# Sensor_Glove_Power-X01.net
KiCad netlist of a schematic drawn in Altium Designer
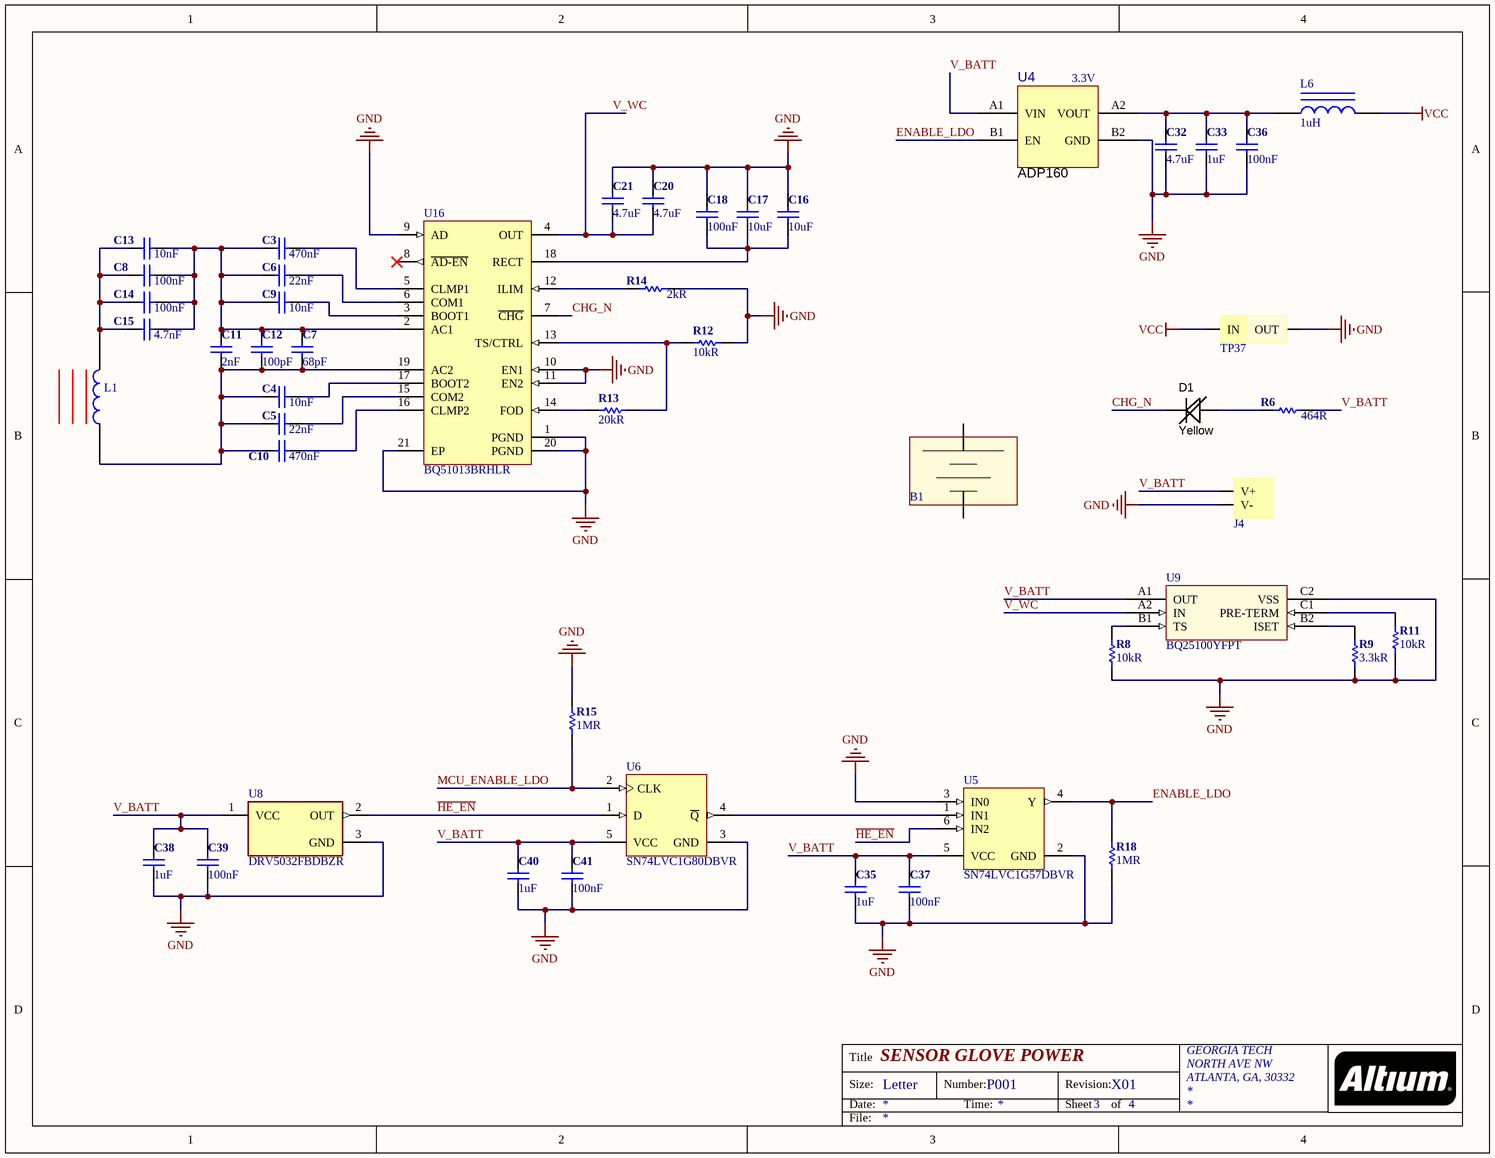
[diagram p0: Sensor_Glove_Power-X01.SchDoc]

(export (version "E")
  (design (tool "Eeschema 10.0.6"))
  (components
    (comp (ref "B1")
      (value "40 mAh BATTERY")
      (footprint "BATTERY")
      (description "Lithium Battery 3.7V 40mAh Rechargeable")
      (fields (field (name "MANUFACTURER") "SparkFun") (field (name "MANUFACTURER PART NUMBER") "PRT-13852"))
      (libsource (lib "Sensor_Glove-X01") (part "BATTERY"))
    )
    (comp (ref "C3")
      (value "470nF")
      (footprint "C0402")
      (fields
        (field (name "MANUFACTURER") "Murata")
        (field (name "MANUFACTURER PART NUMBER") "GRT155R61E474ME01D")
        (field (name "TOLERANCE") "20%")
      )
      (libsource (lib "DB-X01") (part "C-0402(1005)"))
    )
    (comp (ref "C4")
      (value "10nF")
      (footprint "C0402")
      (fields
        (field (name "MANUFACTURER") "KEMET")
        (field (name "MANUFACTURER PART NUMBER") "C0402C103J3RACTU")
        (field (name "TOLERANCE") "5%")
      )
      (libsource (lib "DB-X01") (part "C-0402(1005)"))
    )
    (comp (ref "C5")
      (value "22nF")
      (footprint "C0402")
      (fields
        (field (name "MANUFACTURER") "Murata")
        (field (name "MANUFACTURER PART NUMBER") "GRM155R71E223KA61D")
        (field (name "TOLERANCE") "10%")
      )
      (libsource (lib "DB-X01") (part "C-0402(1005)"))
    )
    (comp (ref "C6")
      (value "22nF")
      (footprint "C0402")
      (fields
        (field (name "MANUFACTURER") "Murata")
        (field (name "MANUFACTURER PART NUMBER") "GRM155R71E223KA61D")
        (field (name "TOLERANCE") "10%")
      )
      (libsource (lib "DB-X01") (part "C-0402(1005)"))
    )
    (comp (ref "C7")
      (value "68pF")
      (footprint "C0402")
      (fields
        (field (name "MANUFACTURER") "KEMET")
        (field (name "MANUFACTURER PART NUMBER") "CBR04C680F3GAC")
        (field (name "TOLERANCE") "1%")
      )
      (libsource (lib "DB-X01") (part "C-0402(1005)"))
    )
    (comp (ref "C8")
      (value "100nF")
      (footprint "C0402")
      (fields
        (field (name "MANUFACTURER") "Taiyo Yuden")
        (field (name "MANUFACTURER PART NUMBER") "TMK105BJ104KV-F")
        (field (name "TOLERANCE") "10%")
      )
      (libsource (lib "DB-X01") (part "C-0402(1005)"))
    )
    (comp (ref "C9")
      (value "10nF")
      (footprint "C0402")
      (fields
        (field (name "MANUFACTURER") "KEMET")
        (field (name "MANUFACTURER PART NUMBER") "C0402C103J3RACTU")
        (field (name "TOLERANCE") "5%")
      )
      (libsource (lib "DB-X01") (part "C-0402(1005)"))
    )
    (comp (ref "C10")
      (value "470nF")
      (footprint "C0402")
      (fields
        (field (name "MANUFACTURER") "Murata")
        (field (name "MANUFACTURER PART NUMBER") "GRT155R61E474ME01D")
        (field (name "TOLERANCE") "20%")
      )
      (libsource (lib "DB-X01") (part "C-0402(1005)"))
    )
    (comp (ref "C11")
      (value "2nF")
      (footprint "C0402")
      (fields
        (field (name "MANUFACTURER") "KEMET")
        (field (name "MANUFACTURER PART NUMBER") "C0402C202J3GACTU")
        (field (name "TOLERANCE") "5%")
      )
      (libsource (lib "DB-X01") (part "C-0402(1005)"))
    )
    (comp (ref "C12")
      (value "100pF")
      (footprint "C0402")
      (fields
        (field (name "MANUFACTURER") "KEMET")
        (field (name "MANUFACTURER PART NUMBER") "CBR04C101F3GAC")
        (field (name "TOLERANCE") "1%")
      )
      (libsource (lib "DB-X01") (part "C-0402(1005)"))
    )
    (comp (ref "C13")
      (value "10nF")
      (footprint "C0402")
      (fields
        (field (name "MANUFACTURER") "Yageo")
        (field (name "MANUFACTURER PART NUMBER") "CC0402JRX7R8BB103")
        (field (name "TOLERANCE") "5%")
      )
      (libsource (lib "DB-X01") (part "C-0402(1005)"))
    )
    (comp (ref "C14")
      (value "100nF")
      (footprint "C0402")
      (fields
        (field (name "MANUFACTURER") "Taiyo Yuden")
        (field (name "MANUFACTURER PART NUMBER") "TMK105BJ104KV-F")
        (field (name "TOLERANCE") "10%")
      )
      (libsource (lib "DB-X01") (part "C-0402(1005)"))
    )
    (comp (ref "C15")
      (value "4.7nF")
      (footprint "C0402")
      (fields
        (field (name "MANUFACTURER") "Yageo")
        (field (name "MANUFACTURER PART NUMBER") "CC0402JRX7R8BB472")
        (field (name "TOLERANCE") "5%")
      )
      (libsource (lib "DB-X01") (part "C-0402(1005)"))
    )
    (comp (ref "C16")
      (value "10uF")
      (footprint "C0603")
      (fields
        (field (name "MANUFACTURER") "Murata")
        (field (name "MANUFACTURER PART NUMBER") "GRM188R61E106MA73J")
        (field (name "TOLERANCE") "20%")
      )
      (libsource (lib "DB-X01") (part "C-0603(1608)"))
    )
    (comp (ref "C17")
      (value "10uF")
      (footprint "C0603")
      (fields
        (field (name "MANUFACTURER") "Murata")
        (field (name "MANUFACTURER PART NUMBER") "GRM188R61E106MA73J")
        (field (name "TOLERANCE") "20%")
      )
      (libsource (lib "DB-X01") (part "C-0603(1608)"))
    )
    (comp (ref "C18")
      (value "100nF")
      (footprint "C0603")
      (fields
        (field (name "MANUFACTURER") "Yageo")
        (field (name "MANUFACTURER PART NUMBER") "CC0402ZRY5V8BB104")
        (field (name "TOLERANCE") "80%")
      )
      (libsource (lib "DB-X01") (part "C-0603(1608)"))
    )
    (comp (ref "C20")
      (value "4.7uF")
      (footprint "C0402")
      (description "0402 10 V 4.7 uF ±20% Tolerance X5R Multilayer Ceramic Chip Capacitor")
      (fields
        (field (name "MANUFACTURER") "Murata")
        (field (name "MANUFACTURER PART NUMBER") "GRM155R61A475MEAAD")
      )
      (libsource (lib "DB-X01") (part "C-0402(1005)"))
    )
    (comp (ref "C21")
      (value "4.7uF")
      (footprint "C0402")
      (description "0402 10 V 4.7 uF ±20% Tolerance X5R Multilayer Ceramic Chip Capacitor")
      (fields
        (field (name "MANUFACTURER") "Murata")
        (field (name "MANUFACTURER PART NUMBER") "GRM155R61A475MEAAD")
      )
      (libsource (lib "DB-X01") (part "C-0402(1005)"))
    )
    (comp (ref "C32")
      (value "4.7uF")
      (footprint "C0402")
      (description "0402 10 V 4.7 uF ±20% Tolerance X5R Multilayer Ceramic Chip Capacitor")
      (fields
        (field (name "MANUFACTURER") "Murata")
        (field (name "MANUFACTURER PART NUMBER") "GRM155R61A475MEAAD")
      )
      (libsource (lib "DB-X01") (part "C-0402(1005)"))
    )
    (comp (ref "C33")
      (value "1uF")
      (footprint "C0402")
      (fields
        (field (name "MANUFACTURER") "Yageo")
        (field (name "MANUFACTURER PART NUMBER") "CC0402MRX5R5BB105")
        (field (name "TOLERANCE") "20%")
      )
      (libsource (lib "DB-X01") (part "C-0402(1005)"))
    )
    (comp (ref "C35")
      (value "1uF")
      (footprint "C0402")
      (fields
        (field (name "MANUFACTURER") "Yageo")
        (field (name "MANUFACTURER PART NUMBER") "CC0402MRX5R5BB105")
        (field (name "TOLERANCE") "20%")
      )
      (libsource (lib "DB-X01") (part "C-0402(1005)"))
    )
    (comp (ref "C36")
      (value "100nF")
      (footprint "C0402")
      (fields
        (field (name "MANUFACTURER") "Taiyo Yuden")
        (field (name "MANUFACTURER PART NUMBER") "TMK105BJ104KV-F")
        (field (name "TOLERANCE") "10%")
      )
      (libsource (lib "DB-X01") (part "C-0402(1005)"))
    )
    (comp (ref "C37")
      (value "100nF")
      (footprint "C0402")
      (fields
        (field (name "MANUFACTURER") "Taiyo Yuden")
        (field (name "MANUFACTURER PART NUMBER") "TMK105BJ104KV-F")
        (field (name "TOLERANCE") "10%")
      )
      (libsource (lib "DB-X01") (part "C-0402(1005)"))
    )
    (comp (ref "C38")
      (value "1uF")
      (footprint "C0402")
      (fields
        (field (name "MANUFACTURER") "Yageo")
        (field (name "MANUFACTURER PART NUMBER") "CC0402MRX5R5BB105")
        (field (name "TOLERANCE") "20%")
      )
      (libsource (lib "DB-X01") (part "C-0402(1005)"))
    )
    (comp (ref "C39")
      (value "100nF")
      (footprint "C0402")
      (fields
        (field (name "MANUFACTURER") "Taiyo Yuden")
        (field (name "MANUFACTURER PART NUMBER") "TMK105BJ104KV-F")
        (field (name "TOLERANCE") "10%")
      )
      (libsource (lib "DB-X01") (part "C-0402(1005)"))
    )
    (comp (ref "C40")
      (value "1uF")
      (footprint "C0402")
      (fields
        (field (name "MANUFACTURER") "Yageo")
        (field (name "MANUFACTURER PART NUMBER") "CC0402MRX5R5BB105")
        (field (name "TOLERANCE") "20%")
      )
      (libsource (lib "DB-X01") (part "C-0402(1005)"))
    )
    (comp (ref "C41")
      (value "100nF")
      (footprint "C0402")
      (fields
        (field (name "MANUFACTURER") "Taiyo Yuden")
        (field (name "MANUFACTURER PART NUMBER") "TMK105BJ104KV-F")
        (field (name "TOLERANCE") "10%")
      )
      (libsource (lib "DB-X01") (part "C-0402(1005)"))
    )
    (comp (ref "D1")
      (value "Yellow")
      (footprint "LED_0402")
      (description "Single Color LED, Super Bright Yellow, Water Clear, 0.8mm")
      (fields
        (field (name "MANUFACTURER") "Kingbright")
        (field (name "MANUFACTURER PART NUMBER") "APHHS1005SYCK")
      )
      (libsource (lib "DB-X01") (part "LED_0402(1005)"))
    )
    (comp (ref "J4")
      (value "JUMPER WITH 40 mAh BATTERY")
      (footprint "JUMPER_BATTERY")
      (description "Lithium Battery 3.7V 40mAh Rechargeable")
      (fields (field (name "MANUFACTURER") "SparkFun") (field (name "MANUFACTURER PART NUMBER") "PRT-13852"))
      (libsource (lib "Sensor_Glove-X01") (part "JUMPER_BATTERY"))
    )
    (comp (ref "L1")
      (value "WIRELESS CHARGING COIL, RECEIVER")
      (footprint "760308101219")
      (description "General Purpose Inductor, 11.8uH, 10%, 1 Element")
      (fields
        (field (name "MANUFACTURER") "Wurth Electronics")
        (field (name "MANUFACTURER PART NUMBER") "760308101219")
      )
      (libsource (lib "DB-X01") (part "WIRELESS_CHARGING_COIL"))
    )
    (comp (ref "L6")
      (value "1uH")
      (footprint "L0402")
      (description "General Purpose Inductor, 1uH, 20%, 1 Element, Ferrite-Core, SMD, 0402")
      (fields
        (field (name "MANUFACTURER") "TDK")
        (field (name "MANUFACTURER PART NUMBER") "MLZ1005M1R0WT000")
      )
      (libsource (lib "DB-X01") (part "Inductor Iron"))
    )
    (comp (ref "R6")
      (value "464R")
      (footprint "R0402")
      (fields
        (field (name "MANUFACTURER") "Yageo")
        (field (name "MANUFACTURER PART NUMBER") "RC0402FR-07464RL")
        (field (name "TOLERANCE") "1%")
      )
      (libsource (lib "DB-X01") (part "R-0402(1005)"))
    )
    (comp (ref "R8")
      (value "10kR")
      (footprint "R0402")
      (fields
        (field (name "MANUFACTURER") "Yageo")
        (field (name "MANUFACTURER PART NUMBER") "AC0402FR-0710KL")
        (field (name "TOLERANCE") "1%")
      )
      (libsource (lib "DB-X01") (part "R-0402(1005)"))
    )
    (comp (ref "R9")
      (value "3.3kR")
      (footprint "R0402")
      (fields
        (field (name "MANUFACTURER") "Yageo")
        (field (name "MANUFACTURER PART NUMBER") "AC0402FR-073K3L")
        (field (name "TOLERANCE") "1%")
      )
      (libsource (lib "DB-X01") (part "R-0402(1005)"))
    )
    (comp (ref "R11")
      (value "10kR")
      (footprint "R0402")
      (fields
        (field (name "MANUFACTURER") "Yageo")
        (field (name "MANUFACTURER PART NUMBER") "AC0402FR-0710KL")
        (field (name "TOLERANCE") "1%")
      )
      (libsource (lib "DB-X01") (part "R-0402(1005)"))
    )
    (comp (ref "R12")
      (value "10kR")
      (footprint "R0402")
      (fields
        (field (name "MANUFACTURER") "Yageo")
        (field (name "MANUFACTURER PART NUMBER") "AC0402FR-0710KL")
        (field (name "TOLERANCE") "1%")
      )
      (libsource (lib "DB-X01") (part "R-0402(1005)"))
    )
    (comp (ref "R13")
      (value "20kR")
      (footprint "R0402")
      (fields
        (field (name "MANUFACTURER") "Yageo")
        (field (name "MANUFACTURER PART NUMBER") "AC0402FR-0720KL")
        (field (name "TOLERANCE") "1%")
      )
      (libsource (lib "DB-X01") (part "R-0402(1005)"))
    )
    (comp (ref "R14")
      (value "2kR")
      (footprint "R0402")
      (fields
        (field (name "MANUFACTURER") "Yageo")
        (field (name "MANUFACTURER PART NUMBER") "AC0402FR-072KL")
        (field (name "TOLERANCE") "1%")
      )
      (libsource (lib "DB-X01") (part "R-0402(1005)"))
    )
    (comp (ref "R15")
      (value "1MR")
      (footprint "R0402")
      (fields
        (field (name "MANUFACTURER") "Yageo")
        (field (name "MANUFACTURER PART NUMBER") "AC0402FR-071ML")
        (field (name "TOLERANCE") "1%")
      )
      (libsource (lib "Sensor_Glove-X01") (part "R-0402(1005)"))
    )
    (comp (ref "R18")
      (value "1MR")
      (footprint "R0402")
      (fields
        (field (name "MANUFACTURER") "Yageo")
        (field (name "MANUFACTURER PART NUMBER") "AC0402FR-071ML")
        (field (name "TOLERANCE") "1%")
      )
      (libsource (lib "Sensor_Glove-X01") (part "R-0402(1005)"))
    )
    (comp (ref "TP37")
      (value "JUMPER")
      (footprint "JUMPER")
      (description "SHUNT LP W/HANDLE 2 POS 30AU")
      (fields
        (field (name "MANUFACTURER") "TE Connectivity")
        (field (name "MANUFACTURER PART NUMBER") "8815452")
      )
      (libsource (lib "DB-X02") (part "JUMPER"))
    )
    (comp (ref "U4")
      (value "ADP160")
      (footprint "ADP160")
      (description "Fixed Positive LDO Regulator, 3.3V, 0.195V Dropout, CMOS, PBGA4")
      (fields
        (field (name "MANUFACTURER") "Analog Devices")
        (field (name "MANUFACTURER PART NUMBER") "ADP160ACBZ-3.3-R7")
        (field (name "OUTPUT VOLTAGE") "3.3V")
      )
      (libsource (lib "DB-X01") (part "ADP160-3_3V"))
    )
    (comp (ref "U5")
      (value "SN74LVC1G57DBVR")
      (footprint "DBV0006A_M")
      (description "CONFIGURABLE MULTIPLE-FUNCTION GATE, DBV0006A, LARGE T&R")
      (fields (field (name "MANUFACTURER") "Texas Instruments"))
      (libsource (lib "Altium Content Vault") (part "TI-SN74XXX1GXX-6"))
    )
    (comp (ref "U6")
      (value "SN74LVC1G80DBVR")
      (footprint "DBV0005A_N")
      (description "Single Positive-Edge-Triggered D-Type Flip-Flop, DBV0005A, LARGE T&R")
      (fields (field (name "MANUFACTURER") "Texas Instruments"))
      (libsource (lib "Altium Content Vault") (part "TI-SN74XXX1G80-5"))
    )
    (comp (ref "U8")
      (value "DRV5032FBDBZR")
      (footprint "FP-DBZ0003A-MFG")
      (description "LP HALL 32FBDBZR")
      (fields (field (name "MANUFACTURER") "Texas Instruments"))
      (libsource (lib "Altium Content Vault") (part "2ac151be60cf6bda0d169f73a696793"))
    )
    (comp (ref "U9")
      (value "BQ25100YFPT")
      (footprint "YZP0006")
      (description "Power Supply Support Circuit")
      (fields (field (name "MANUFACTURER") "Texas Instruments"))
      (libsource (lib "Sensor_Glove-X01") (part "BQ25100YFPT"))
    )
    (comp (ref "U16")
      (value "BQ51013BRHLR")
      (footprint "BQ51013BRHLR")
      (fields (field (name "MANUFACTURER") "Texas Instruments"))
      (libsource (lib "DB-X01") (part "TI-BQ51013B-RHL20"))
    )
  )
  (nets
    (net (code "1") (name "/CHG_N") (class "Default")
      (node (ref "D1") (pin "K") (pinfunction "K_K") (pintype "passive"))
      (node (ref "U16") (pin "7") (pinfunction "~{CHG}_7") (pintype "open_collector"))
    )
    (net (code "2") (name "/ENABLE_LDO") (class "Default")
      (node (ref "R18") (pin "1") (pinfunction "1_1") (pintype "passive"))
      (node (ref "U4") (pin "B1") (pinfunction "EN_B1") (pintype "passive"))
      (node (ref "U5") (pin "4") (pinfunction "Y_4") (pintype "output"))
    )
    (net (code "3") (name "/MCU_ENABLE_LDO") (class "Default")
      (node (ref "R15") (pin "2") (pinfunction "2_2") (pintype "passive"))
      (node (ref "U6") (pin "2") (pinfunction "CLK_2") (pintype "input"))
    )
    (net (code "4") (name "/V_BATT") (class "Default")
      (node (ref "C35") (pin "1") (pinfunction "1_1") (pintype "passive"))
      (node (ref "C37") (pin "2") (pinfunction "2_2") (pintype "passive"))
      (node (ref "C38") (pin "1") (pinfunction "1_1") (pintype "passive"))
      (node (ref "C39") (pin "2") (pinfunction "2_2") (pintype "passive"))
      (node (ref "C40") (pin "1") (pinfunction "1_1") (pintype "passive"))
      (node (ref "C41") (pin "2") (pinfunction "2_2") (pintype "passive"))
      (node (ref "J4") (pin "1") (pinfunction "V+_1") (pintype "passive"))
      (node (ref "R6") (pin "2") (pinfunction "2_2") (pintype "passive"))
      (node (ref "U4") (pin "A1") (pinfunction "VIN_A1") (pintype "passive"))
      (node (ref "U5") (pin "5") (pinfunction "VCC_5") (pintype "power_in"))
      (node (ref "U6") (pin "5") (pinfunction "VCC_5") (pintype "power_in"))
      (node (ref "U8") (pin "1") (pinfunction "VCC_1") (pintype "power_in"))
      (node (ref "U9") (pin "A1") (pinfunction "OUT_A1") (pintype "power_in"))
    )
    (net (code "5") (name "/V_WC") (class "Default")
      (node (ref "C20") (pin "2") (pinfunction "2_2") (pintype "passive"))
      (node (ref "C21") (pin "2") (pinfunction "2_2") (pintype "passive"))
      (node (ref "U16") (pin "4") (pinfunction "OUT_4") (pintype "power_in"))
      (node (ref "U9") (pin "A2") (pinfunction "IN_A2") (pintype "input"))
    )
    (net (code "6") (name "/~{HE_EN}") (class "Default")
      (node (ref "U5") (pin "6") (pinfunction "IN2_6") (pintype "input"))
      (node (ref "U6") (pin "1") (pinfunction "D_1") (pintype "input"))
      (node (ref "U8") (pin "2") (pinfunction "OUT_2") (pintype "output"))
    )
    (net (code "7") (name "GND") (class "Default")
      (node (ref "C16") (pin "2") (pinfunction "2_2") (pintype "passive"))
      (node (ref "C17") (pin "2") (pinfunction "2_2") (pintype "passive"))
      (node (ref "C18") (pin "2") (pinfunction "2_2") (pintype "passive"))
      (node (ref "C20") (pin "1") (pinfunction "1_1") (pintype "passive"))
      (node (ref "C21") (pin "1") (pinfunction "1_1") (pintype "passive"))
      (node (ref "C32") (pin "2") (pinfunction "2_2") (pintype "passive"))
      (node (ref "C33") (pin "2") (pinfunction "2_2") (pintype "passive"))
      (node (ref "C35") (pin "2") (pinfunction "2_2") (pintype "passive"))
      (node (ref "C36") (pin "1") (pinfunction "1_1") (pintype "passive"))
      (node (ref "C37") (pin "1") (pinfunction "1_1") (pintype "passive"))
      (node (ref "C38") (pin "2") (pinfunction "2_2") (pintype "passive"))
      (node (ref "C39") (pin "1") (pinfunction "1_1") (pintype "passive"))
      (node (ref "C40") (pin "2") (pinfunction "2_2") (pintype "passive"))
      (node (ref "C41") (pin "1") (pinfunction "1_1") (pintype "passive"))
      (node (ref "J4") (pin "2") (pinfunction "V-_2") (pintype "passive"))
      (node (ref "R11") (pin "1") (pinfunction "1_1") (pintype "passive"))
      (node (ref "R12") (pin "2") (pinfunction "2_2") (pintype "passive"))
      (node (ref "R14") (pin "2") (pinfunction "2_2") (pintype "passive"))
      (node (ref "R15") (pin "1") (pinfunction "1_1") (pintype "passive"))
      (node (ref "R18") (pin "2") (pinfunction "2_2") (pintype "passive"))
      (node (ref "R8") (pin "1") (pinfunction "1_1") (pintype "passive"))
      (node (ref "R9") (pin "1") (pinfunction "1_1") (pintype "passive"))
      (node (ref "TP37") (pin "2") (pinfunction "OUT_2") (pintype "passive"))
      (node (ref "U16") (pin "1") (pinfunction "PGND_1") (pintype "power_in"))
      (node (ref "U16") (pin "10") (pinfunction "EN1_10") (pintype "input"))
      (node (ref "U16") (pin "11") (pinfunction "EN2_11") (pintype "input"))
      (node (ref "U16") (pin "20") (pinfunction "PGND_20") (pintype "power_in"))
      (node (ref "U16") (pin "21") (pinfunction "EP_21") (pintype "passive"))
      (node (ref "U16") (pin "9") (pinfunction "AD_9") (pintype "input"))
      (node (ref "U4") (pin "B2") (pinfunction "GND_B2") (pintype "passive"))
      (node (ref "U5") (pin "2") (pinfunction "GND_2") (pintype "power_in"))
      (node (ref "U5") (pin "3") (pinfunction "IN0_3") (pintype "input"))
      (node (ref "U6") (pin "3") (pinfunction "GND_3") (pintype "power_in"))
      (node (ref "U8") (pin "3") (pinfunction "GND_3") (pintype "power_in"))
      (node (ref "U9") (pin "C2") (pinfunction "VSS_C2") (pintype "power_in"))
    )
    (net (code "8") (name "Net-(C13-Pad1)") (class "Default")
      (node (ref "C13") (pin "1") (pinfunction "1_1") (pintype "passive"))
      (node (ref "C14") (pin "1") (pinfunction "1_1") (pintype "passive"))
      (node (ref "C15") (pin "1") (pinfunction "1_1") (pintype "passive"))
      (node (ref "C8") (pin "1") (pinfunction "1_1") (pintype "passive"))
      (node (ref "L1") (pin "2") (pinfunction "2_2") (pintype "passive"))
    )
    (net (code "9") (name "Net-(D1-PadA)") (class "Default")
      (node (ref "D1") (pin "A") (pinfunction "A_A") (pintype "passive"))
      (node (ref "R6") (pin "1") (pinfunction "1_1") (pintype "passive"))
    )
    (net (code "10") (name "Net-(U4-VOUT)") (class "Default")
      (node (ref "C32") (pin "1") (pinfunction "1_1") (pintype "passive"))
      (node (ref "C33") (pin "1") (pinfunction "1_1") (pintype "passive"))
      (node (ref "C36") (pin "2") (pinfunction "2_2") (pintype "passive"))
      (node (ref "L6") (pin "1") (pinfunction "1_1") (pintype "passive"))
      (node (ref "U4") (pin "A2") (pinfunction "VOUT_A2") (pintype "passive"))
    )
    (net (code "11") (name "Net-(U5-IN1)") (class "Default")
      (node (ref "U5") (pin "1") (pinfunction "IN1_1") (pintype "input"))
      (node (ref "U6") (pin "4") (pinfunction "~{Q}_4") (pintype "output"))
    )
    (net (code "12") (name "Net-(U9-ISET)") (class "Default")
      (node (ref "R9") (pin "2") (pinfunction "2_2") (pintype "passive"))
      (node (ref "U9") (pin "B2") (pinfunction "ISET_B2") (pintype "input"))
    )
    (net (code "13") (name "Net-(U9-PRE-TERM)") (class "Default")
      (node (ref "R11") (pin "2") (pinfunction "2_2") (pintype "passive"))
      (node (ref "U9") (pin "C1") (pinfunction "PRE-TERM_C1") (pintype "input"))
    )
    (net (code "14") (name "Net-(U9-TS)") (class "Default")
      (node (ref "R8") (pin "2") (pinfunction "2_2") (pintype "passive"))
      (node (ref "U9") (pin "B1") (pinfunction "TS_B1") (pintype "input"))
    )
    (net (code "15") (name "Net-(U16-AC1)") (class "Default")
      (node (ref "C11") (pin "1") (pinfunction "1_1") (pintype "passive"))
      (node (ref "C12") (pin "1") (pinfunction "1_1") (pintype "passive"))
      (node (ref "C13") (pin "2") (pinfunction "2_2") (pintype "passive"))
      (node (ref "C14") (pin "2") (pinfunction "2_2") (pintype "passive"))
      (node (ref "C15") (pin "2") (pinfunction "2_2") (pintype "passive"))
      (node (ref "C3") (pin "1") (pinfunction "1_1") (pintype "passive"))
      (node (ref "C6") (pin "1") (pinfunction "1_1") (pintype "passive"))
      (node (ref "C7") (pin "1") (pinfunction "1_1") (pintype "passive"))
      (node (ref "C8") (pin "2") (pinfunction "2_2") (pintype "passive"))
      (node (ref "C9") (pin "1") (pinfunction "1_1") (pintype "passive"))
      (node (ref "U16") (pin "2") (pinfunction "AC1_2") (pintype "power_in"))
    )
    (net (code "16") (name "Net-(U16-AC2)") (class "Default")
      (node (ref "C10") (pin "1") (pinfunction "1_1") (pintype "passive"))
      (node (ref "C11") (pin "2") (pinfunction "2_2") (pintype "passive"))
      (node (ref "C12") (pin "2") (pinfunction "2_2") (pintype "passive"))
      (node (ref "C4") (pin "1") (pinfunction "1_1") (pintype "passive"))
      (node (ref "C5") (pin "1") (pinfunction "1_1") (pintype "passive"))
      (node (ref "C7") (pin "2") (pinfunction "2_2") (pintype "passive"))
      (node (ref "L1") (pin "1") (pinfunction "1_1") (pintype "passive"))
      (node (ref "U16") (pin "19") (pinfunction "AC2_19") (pintype "power_in"))
    )
    (net (code "17") (name "Net-(U16-BOOT1)") (class "Default")
      (node (ref "C9") (pin "2") (pinfunction "2_2") (pintype "passive"))
      (node (ref "U16") (pin "3") (pinfunction "BOOT1_3") (pintype "passive"))
    )
    (net (code "18") (name "Net-(U16-BOOT2)") (class "Default")
      (node (ref "C4") (pin "2") (pinfunction "2_2") (pintype "passive"))
      (node (ref "U16") (pin "17") (pinfunction "BOOT2_17") (pintype "passive"))
    )
    (net (code "19") (name "Net-(U16-CLMP1)") (class "Default")
      (node (ref "C3") (pin "2") (pinfunction "2_2") (pintype "passive"))
      (node (ref "U16") (pin "5") (pinfunction "CLMP1_5") (pintype "open_collector"))
    )
    (net (code "20") (name "Net-(U16-CLMP2)") (class "Default")
      (node (ref "C10") (pin "2") (pinfunction "2_2") (pintype "passive"))
      (node (ref "U16") (pin "16") (pinfunction "CLMP2_16") (pintype "open_collector"))
    )
    (net (code "21") (name "Net-(U16-COM1)") (class "Default")
      (node (ref "C6") (pin "2") (pinfunction "2_2") (pintype "passive"))
      (node (ref "U16") (pin "6") (pinfunction "COM1_6") (pintype "open_collector"))
    )
    (net (code "22") (name "Net-(U16-COM2)") (class "Default")
      (node (ref "C5") (pin "2") (pinfunction "2_2") (pintype "passive"))
      (node (ref "U16") (pin "15") (pinfunction "COM2_15") (pintype "open_collector"))
    )
    (net (code "23") (name "Net-(U16-FOD)") (class "Default")
      (node (ref "R13") (pin "1") (pinfunction "1_1") (pintype "passive"))
      (node (ref "U16") (pin "14") (pinfunction "FOD_14") (pintype "input"))
    )
    (net (code "24") (name "Net-(U16-ILIM)") (class "Default")
      (node (ref "R14") (pin "1") (pinfunction "1_1") (pintype "passive"))
      (node (ref "U16") (pin "12") (pinfunction "ILIM_12") (pintype "input"))
    )
    (net (code "25") (name "Net-(U16-RECT)") (class "Default")
      (node (ref "C16") (pin "1") (pinfunction "1_1") (pintype "passive"))
      (node (ref "C17") (pin "1") (pinfunction "1_1") (pintype "passive"))
      (node (ref "C18") (pin "1") (pinfunction "1_1") (pintype "passive"))
      (node (ref "U16") (pin "18") (pinfunction "RECT_18") (pintype "passive"))
    )
    (net (code "26") (name "Net-(U16-TS{slash}CTRL)") (class "Default")
      (node (ref "R12") (pin "1") (pinfunction "1_1") (pintype "passive"))
      (node (ref "R13") (pin "2") (pinfunction "2_2") (pintype "passive"))
      (node (ref "U16") (pin "13") (pinfunction "TS/CTRL_13") (pintype "input"))
    )
    (net (code "27") (name "VCC") (class "Default")
      (node (ref "L6") (pin "2") (pinfunction "2_2") (pintype "passive"))
      (node (ref "TP37") (pin "1") (pinfunction "IN_1") (pintype "passive"))
    )
    (net (code "28") (name "unconnected-(U16-~{AD-EN}-Pad8)") (class "Default")
      (node (ref "U16") (pin "8") (pinfunction "~{AD-EN}_8") (pintype "output+no_connect"))
    )
  )
)
